# CRD.net
KiCad netlist of a schematic drawn in EAGLE
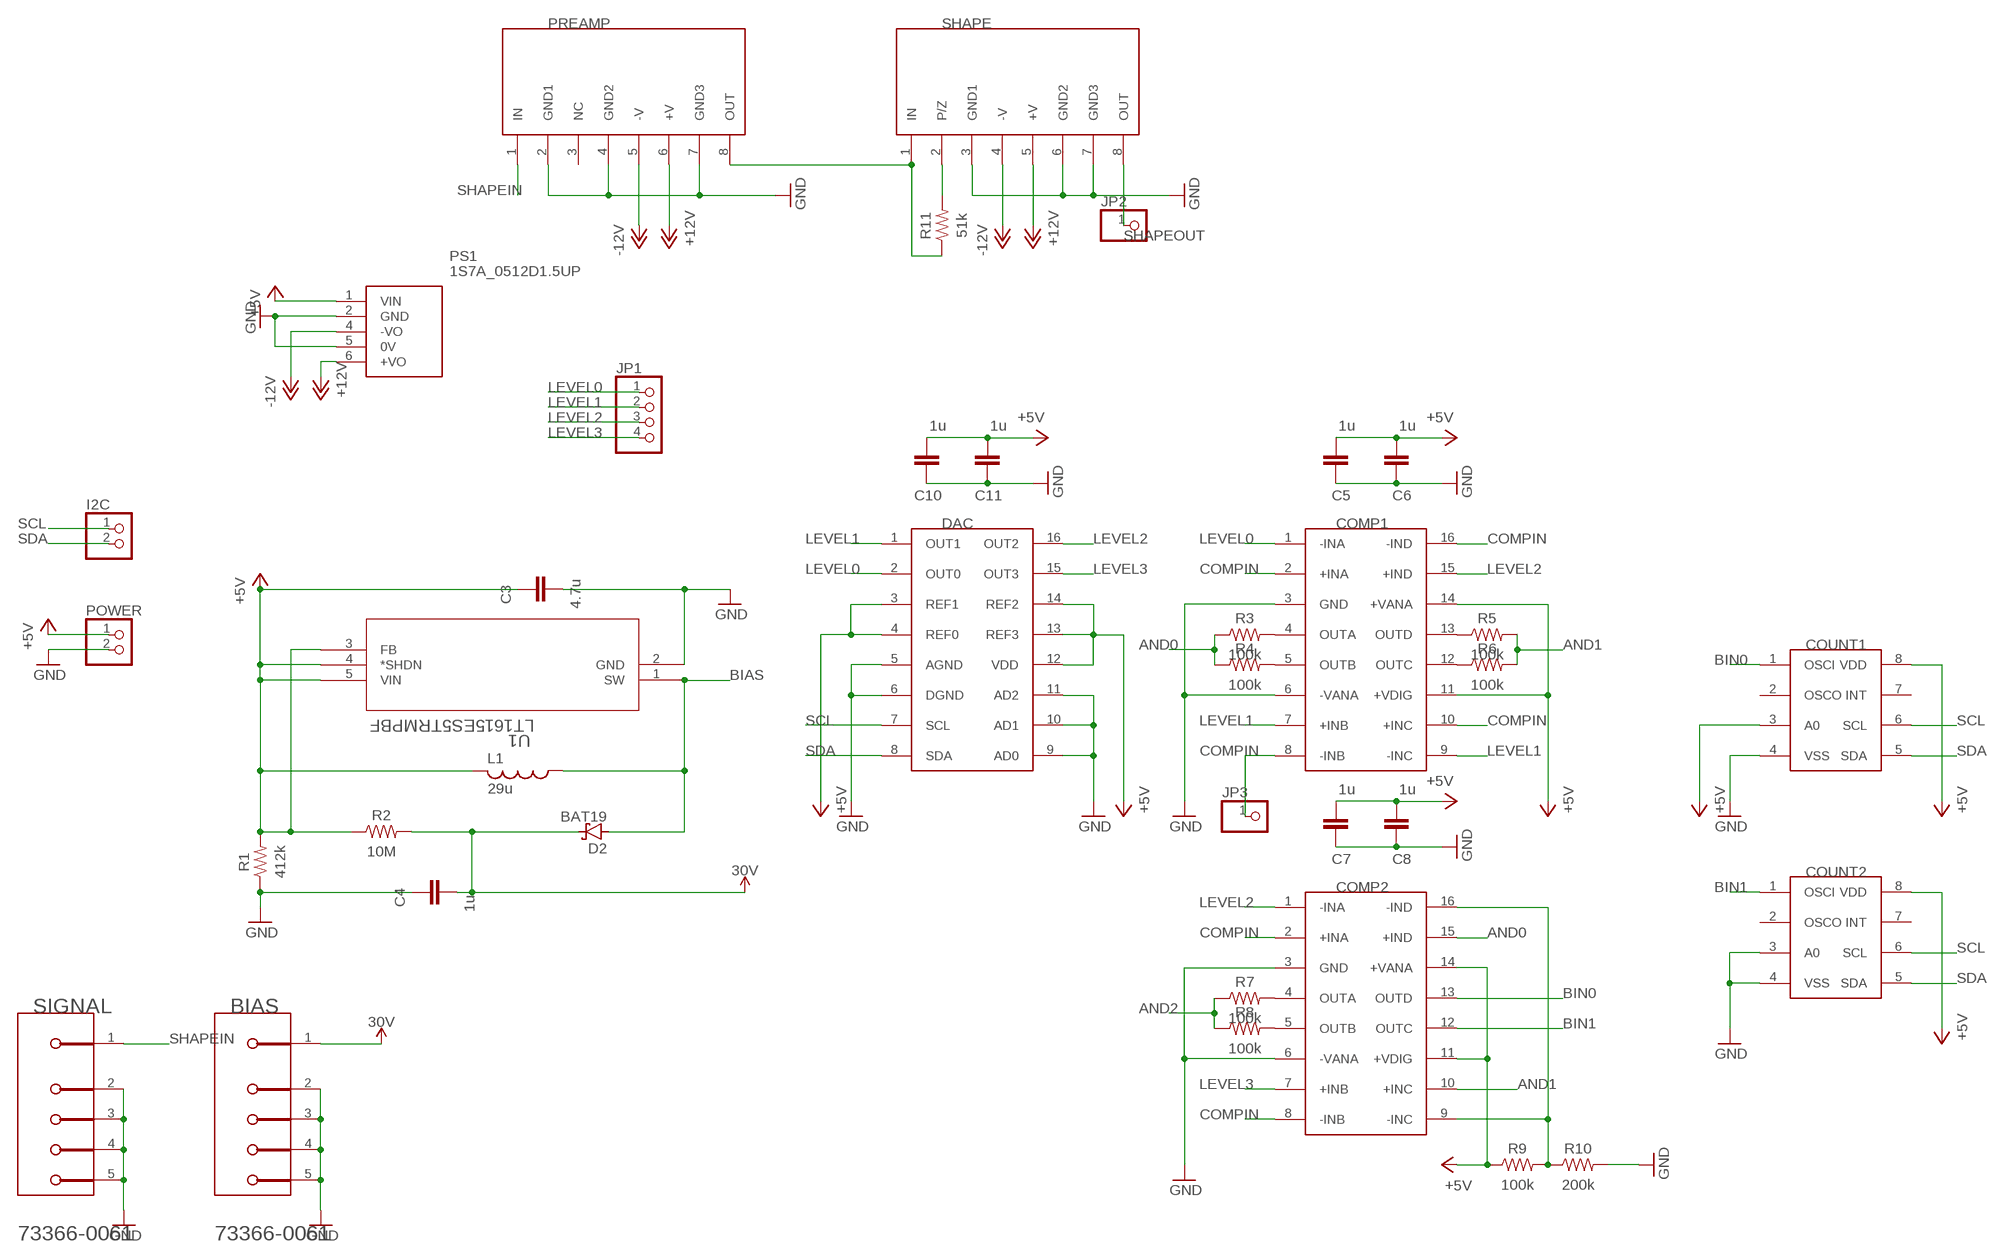
[diagram p0: schematic, sheet 1]

(export (version "E")
  (design (tool "Eeschema 10.0.6"))
  (components
    (comp (ref "BIAS")
      (value "MOLEX_73366-0061MOLEX_73366-0061_0_0")
      (footprint "eagle-import:MOLEX_73366-0061_0")
      (fields
        (field (name "DIGIKEY_PART_NUMBER") "WM5541-ND")
        (field (name "MF") "Molex")
        (field (name "MOUSER_PART_NUMBER") "538-73366-0061")
      )
      (libsource (lib "eagle-import") (part "MOLEX_73366-0061MOLEX_73366-0061_0_0"))
    )
    (comp (ref "C3")
      (value "4.7u")
      (footprint "eagle-import:CAP_1206")
      (fields
        (field (name "DIGIKEY_PART_NUMBER") "GRM31CR60J107ME39L")
        (field (name "MANUFACTURER") "Murata Electronics North America")
        (field (name "CREATED_BY") "PCBLayout.com")
      )
      (libsource (lib "eagle-import") (part "GRM31CR60J107ME39L"))
    )
    (comp (ref "C4")
      (value "1u")
      (footprint "eagle-import:CAP_1206")
      (fields
        (field (name "DIGIKEY_PART_NUMBER") "GRM31CR60J107ME39L")
        (field (name "MANUFACTURER") "Murata Electronics North America")
        (field (name "CREATED_BY") "PCBLayout.com")
      )
      (libsource (lib "eagle-import") (part "GRM31CR60J107ME39L"))
    )
    (comp (ref "C5")
      (value "1u")
      (footprint "eagle-import:CAP_1206")
      (fields
        (field (name "DIGIKEY_PART_NUMBER") "GRM31CR60J107ME39L")
        (field (name "MANUFACTURER") "Murata Electronics North America")
        (field (name "CREATED_BY") "PCBLayout.com")
      )
      (libsource (lib "eagle-import") (part "GRM31CR60J107ME39L"))
    )
    (comp (ref "C6")
      (value "1u")
      (footprint "eagle-import:CAP_1206")
      (fields
        (field (name "DIGIKEY_PART_NUMBER") "GRM31CR60J107ME39L")
        (field (name "MANUFACTURER") "Murata Electronics North America")
        (field (name "CREATED_BY") "PCBLayout.com")
      )
      (libsource (lib "eagle-import") (part "GRM31CR60J107ME39L"))
    )
    (comp (ref "C7")
      (value "1u")
      (footprint "eagle-import:CAP_1206")
      (fields
        (field (name "DIGIKEY_PART_NUMBER") "GRM31CR60J107ME39L")
        (field (name "MANUFACTURER") "Murata Electronics North America")
        (field (name "CREATED_BY") "PCBLayout.com")
      )
      (libsource (lib "eagle-import") (part "GRM31CR60J107ME39L"))
    )
    (comp (ref "C8")
      (value "1u")
      (footprint "eagle-import:CAP_1206")
      (fields
        (field (name "DIGIKEY_PART_NUMBER") "GRM31CR60J107ME39L")
        (field (name "MANUFACTURER") "Murata Electronics North America")
        (field (name "CREATED_BY") "PCBLayout.com")
      )
      (libsource (lib "eagle-import") (part "GRM31CR60J107ME39L"))
    )
    (comp (ref "C10")
      (value "1u")
      (footprint "eagle-import:CAP_1206")
      (fields
        (field (name "DIGIKEY_PART_NUMBER") "GRM31CR60J107ME39L")
        (field (name "MANUFACTURER") "Murata Electronics North America")
        (field (name "CREATED_BY") "PCBLayout.com")
      )
      (libsource (lib "eagle-import") (part "GRM31CR60J107ME39L"))
    )
    (comp (ref "C11")
      (value "1u")
      (footprint "eagle-import:CAP_1206")
      (fields
        (field (name "DIGIKEY_PART_NUMBER") "GRM31CR60J107ME39L")
        (field (name "MANUFACTURER") "Murata Electronics North America")
        (field (name "CREATED_BY") "PCBLayout.com")
      )
      (libsource (lib "eagle-import") (part "GRM31CR60J107ME39L"))
    )
    (comp (ref "COMP1")
      (value "AD8564ARZ")
      (footprint "eagle-import:SOIC127P1032X265-16N")
      (libsource (lib "eagle-import") (part "AD8564ARZ"))
    )
    (comp (ref "COMP2")
      (value "AD8564ARZ")
      (footprint "eagle-import:SOIC127P1032X265-16N")
      (libsource (lib "eagle-import") (part "AD8564ARZ"))
    )
    (comp (ref "COUNT1")
      (value "PCF8583")
      (footprint "eagle-import:SOIC127P1032X265-8N")
      (libsource (lib "eagle-import") (part "PCF8583"))
    )
    (comp (ref "COUNT2")
      (value "PCF8583")
      (footprint "eagle-import:SOIC127P1032X265-8N")
      (libsource (lib "eagle-import") (part "PCF8583"))
    )
    (comp (ref "D2")
      (value "BAT19")
      (footprint "eagle-import:DO35-10")
      (libsource (lib "eagle-import") (part "BAT19"))
    )
    (comp (ref "DAC")
      (value "MAX520BEWE+")
      (footprint "eagle-import:SOIC127P1032X265-16N")
      (libsource (lib "eagle-import") (part "MAX520BEWE+"))
    )
    (comp (ref "I2C")
      (value "PINHD-1X2")
      (footprint "eagle-import:1X02")
      (libsource (lib "eagle-import") (part "PINHD-1X2"))
    )
    (comp (ref "JP1")
      (value "PINHD-1X4")
      (footprint "eagle-import:1X04")
      (libsource (lib "eagle-import") (part "PINHD-1X4"))
    )
    (comp (ref "JP2")
      (value "PINHD-1X1")
      (footprint "eagle-import:1X01")
      (libsource (lib "eagle-import") (part "PINHD-1X1"))
    )
    (comp (ref "JP3")
      (value "PINHD-1X1")
      (footprint "eagle-import:1X01")
      (libsource (lib "eagle-import") (part "PINHD-1X1"))
    )
    (comp (ref "L1")
      (value "29u")
      (footprint "eagle-import:L1812")
      (libsource (lib "eagle-import") (part "L-USL1812"))
    )
    (comp (ref "POWER")
      (value "PINHD-1X2")
      (footprint "eagle-import:1X02")
      (libsource (lib "eagle-import") (part "PINHD-1X2"))
    )
    (comp (ref "PREAMP")
      (value "CR-113")
      (footprint "eagle-import:HDRV8W64P254_1X8_1016X508X838B")
      (libsource (lib "eagle-import") (part "CR-113"))
    )
    (comp (ref "PS1")
      (value "1S7A_0512D1.5UP")
      (footprint "eagle-import:1S7A_0505D15UP")
      (libsource (lib "eagle-import") (part "1S7A_0512D1.5UP"))
    )
    (comp (ref "R1")
      (value "412k")
      (footprint "eagle-import:RESAD1176W63L850D250B")
      (libsource (lib "eagle-import") (part "R-USAXIAL-11.7MM-PITCH_"))
    )
    (comp (ref "R2")
      (value "10M")
      (footprint "eagle-import:RESAD1176W63L850D250B")
      (libsource (lib "eagle-import") (part "R-USAXIAL-11.7MM-PITCH_"))
    )
    (comp (ref "R3")
      (value "100k")
      (footprint "eagle-import:RESAD1176W63L850D250B")
      (libsource (lib "eagle-import") (part "R-USAXIAL-11.7MM-PITCH_"))
    )
    (comp (ref "R4")
      (value "100k")
      (footprint "eagle-import:RESAD1176W63L850D250B")
      (libsource (lib "eagle-import") (part "R-USAXIAL-11.7MM-PITCH_"))
    )
    (comp (ref "R5")
      (value "100k")
      (footprint "eagle-import:RESAD1176W63L850D250B")
      (libsource (lib "eagle-import") (part "R-USAXIAL-11.7MM-PITCH_"))
    )
    (comp (ref "R6")
      (value "100k")
      (footprint "eagle-import:RESAD1176W63L850D250B")
      (libsource (lib "eagle-import") (part "R-USAXIAL-11.7MM-PITCH_"))
    )
    (comp (ref "R7")
      (value "100k")
      (footprint "eagle-import:RESAD1176W63L850D250B")
      (libsource (lib "eagle-import") (part "R-USAXIAL-11.7MM-PITCH_"))
    )
    (comp (ref "R8")
      (value "100k")
      (footprint "eagle-import:RESAD1176W63L850D250B")
      (libsource (lib "eagle-import") (part "R-USAXIAL-11.7MM-PITCH_"))
    )
    (comp (ref "R9")
      (value "100k")
      (footprint "eagle-import:RESAD1176W63L850D250B")
      (libsource (lib "eagle-import") (part "R-USAXIAL-11.7MM-PITCH_"))
    )
    (comp (ref "R10")
      (value "200k")
      (footprint "eagle-import:RESAD1176W63L850D250B")
      (libsource (lib "eagle-import") (part "R-USAXIAL-11.7MM-PITCH_"))
    )
    (comp (ref "R11")
      (value "51k")
      (footprint "eagle-import:RESAD1176W63L850D250B")
      (libsource (lib "eagle-import") (part "R-USAXIAL-11.7MM-PITCH_"))
    )
    (comp (ref "SHAPE")
      (value "CR-200")
      (footprint "eagle-import:HDRV8W64P254_1X8_1016X508X838B")
      (libsource (lib "eagle-import") (part "CR-200"))
    )
    (comp (ref "SIGNAL")
      (value "MOLEX_73366-0061MOLEX_73366-0061_0_0")
      (footprint "eagle-import:MOLEX_73366-0061_0")
      (fields
        (field (name "DIGIKEY_PART_NUMBER") "WM5541-ND")
        (field (name "MF") "Molex")
        (field (name "MOUSER_PART_NUMBER") "538-73366-0061")
      )
      (libsource (lib "eagle-import") (part "MOLEX_73366-0061MOLEX_73366-0061_0_0"))
    )
    (comp (ref "U1")
      (value "LT1615ES5TRMPBF")
      (footprint "eagle-import:SOT-5_S")
      (fields
        (field (name "DIGI-KEY_PART_NUMBER") "LT1615ES5#TRMPBFCT-ND")
        (field (name "MF") "Analog Devices")
        (field (name "MP") "LT1615ES5#TRMPBF")
      )
      (libsource (lib "eagle-import") (part "LT1615ES5TRMPBF"))
    )
  )
  (nets
    (net (code "1") (name "+5V") (class "Default")
      (node (ref "C10") (pin "2") (pinfunction "2_2") (pintype "passive"))
      (node (ref "C11") (pin "2") (pinfunction "2_2") (pintype "passive"))
      (node (ref "C3") (pin "1") (pinfunction "1_1") (pintype "passive"))
      (node (ref "C5") (pin "2") (pinfunction "2_2") (pintype "passive"))
      (node (ref "C6") (pin "2") (pinfunction "2_2") (pintype "passive"))
      (node (ref "C7") (pin "2") (pinfunction "2_2") (pintype "passive"))
      (node (ref "C8") (pin "2") (pinfunction "2_2") (pintype "passive"))
      (node (ref "COMP1") (pin "11") (pinfunction "+VDIG_11") (pintype "bidirectional"))
      (node (ref "COMP1") (pin "14") (pinfunction "+VANA_14") (pintype "bidirectional"))
      (node (ref "COMP2") (pin "11") (pinfunction "+VDIG_11") (pintype "bidirectional"))
      (node (ref "COMP2") (pin "14") (pinfunction "+VANA_14") (pintype "bidirectional"))
      (node (ref "COUNT1") (pin "3") (pinfunction "A0_3") (pintype "bidirectional"))
      (node (ref "COUNT1") (pin "8") (pinfunction "VDD_8") (pintype "bidirectional"))
      (node (ref "COUNT2") (pin "8") (pinfunction "VDD_8") (pintype "bidirectional"))
      (node (ref "DAC") (pin "12") (pinfunction "VDD_12") (pintype "bidirectional"))
      (node (ref "DAC") (pin "13") (pinfunction "REF3_13") (pintype "bidirectional"))
      (node (ref "DAC") (pin "14") (pinfunction "REF2_14") (pintype "bidirectional"))
      (node (ref "DAC") (pin "3") (pinfunction "REF1_3") (pintype "bidirectional"))
      (node (ref "DAC") (pin "4") (pinfunction "REF0_4") (pintype "bidirectional"))
      (node (ref "L1") (pin "2") (pinfunction "2_2") (pintype "passive"))
      (node (ref "POWER") (pin "1") (pinfunction "1_1") (pintype "passive"))
      (node (ref "PS1") (pin "1") (pinfunction "VIN_1") (pintype "bidirectional"))
      (node (ref "R1") (pin "2") (pinfunction "2_2") (pintype "passive"))
      (node (ref "R2") (pin "1") (pinfunction "1_1") (pintype "passive"))
      (node (ref "R9") (pin "1") (pinfunction "1_1") (pintype "passive"))
      (node (ref "U1") (pin "3") (pinfunction "FB_3") (pintype "passive"))
      (node (ref "U1") (pin "4") (pinfunction "*SHDN_4") (pintype "passive"))
      (node (ref "U1") (pin "5") (pinfunction "VIN_5") (pintype "input"))
    )
    (net (code "2") (name "+12V") (class "Default")
      (node (ref "PREAMP") (pin "6") (pinfunction "+V_6") (pintype "bidirectional"))
      (node (ref "PS1") (pin "6") (pinfunction "+VO_6") (pintype "bidirectional"))
      (node (ref "SHAPE") (pin "5") (pinfunction "+V_5") (pintype "bidirectional"))
    )
    (net (code "3") (name "-12V") (class "Default")
      (node (ref "PREAMP") (pin "5") (pinfunction "-V_5") (pintype "bidirectional"))
      (node (ref "PS1") (pin "4") (pinfunction "-VO_4") (pintype "bidirectional"))
      (node (ref "SHAPE") (pin "4") (pinfunction "-V_4") (pintype "bidirectional"))
    )
    (net (code "4") (name "/AND0") (class "Default")
      (node (ref "COMP2") (pin "15") (pinfunction "+IND_15") (pintype "bidirectional"))
      (node (ref "R3") (pin "1") (pinfunction "1_1") (pintype "passive"))
      (node (ref "R4") (pin "1") (pinfunction "1_1") (pintype "passive"))
    )
    (net (code "5") (name "/AND1") (class "Default")
      (node (ref "COMP2") (pin "10") (pinfunction "+INC_10") (pintype "bidirectional"))
      (node (ref "R5") (pin "2") (pinfunction "2_2") (pintype "passive"))
      (node (ref "R6") (pin "2") (pinfunction "2_2") (pintype "passive"))
    )
    (net (code "6") (name "/AND2") (class "Default")
      (node (ref "R7") (pin "1") (pinfunction "1_1") (pintype "passive"))
      (node (ref "R8") (pin "1") (pinfunction "1_1") (pintype "passive"))
    )
    (net (code "7") (name "/BIAS") (class "Default")
      (node (ref "D2") (pin "A") (pinfunction "A_A") (pintype "passive"))
      (node (ref "L1") (pin "1") (pinfunction "1_1") (pintype "passive"))
      (node (ref "U1") (pin "1") (pinfunction "SW_1") (pintype "passive"))
    )
    (net (code "8") (name "/BIN0") (class "Default")
      (node (ref "COMP2") (pin "13") (pinfunction "OUTD_13") (pintype "bidirectional"))
      (node (ref "COUNT1") (pin "1") (pinfunction "OSCI_1") (pintype "bidirectional"))
    )
    (net (code "9") (name "/BIN1") (class "Default")
      (node (ref "COMP2") (pin "12") (pinfunction "OUTC_12") (pintype "bidirectional"))
      (node (ref "COUNT2") (pin "1") (pinfunction "OSCI_1") (pintype "bidirectional"))
    )
    (net (code "10") (name "/COMPIN") (class "Default")
      (node (ref "COMP1") (pin "10") (pinfunction "+INC_10") (pintype "bidirectional"))
      (node (ref "COMP1") (pin "16") (pinfunction "-IND_16") (pintype "bidirectional"))
      (node (ref "COMP1") (pin "2") (pinfunction "+INA_2") (pintype "bidirectional"))
      (node (ref "COMP1") (pin "8") (pinfunction "-INB_8") (pintype "bidirectional"))
      (node (ref "COMP2") (pin "2") (pinfunction "+INA_2") (pintype "bidirectional"))
      (node (ref "COMP2") (pin "8") (pinfunction "-INB_8") (pintype "bidirectional"))
      (node (ref "JP3") (pin "1") (pinfunction "1_1") (pintype "passive"))
    )
    (net (code "11") (name "/LEVEL0") (class "Default")
      (node (ref "COMP1") (pin "1") (pinfunction "-INA_1") (pintype "bidirectional"))
      (node (ref "DAC") (pin "2") (pinfunction "OUT0_2") (pintype "bidirectional"))
      (node (ref "JP1") (pin "1") (pinfunction "1_1") (pintype "passive"))
    )
    (net (code "12") (name "/LEVEL1") (class "Default")
      (node (ref "COMP1") (pin "7") (pinfunction "+INB_7") (pintype "bidirectional"))
      (node (ref "COMP1") (pin "9") (pinfunction "-INC_9") (pintype "bidirectional"))
      (node (ref "DAC") (pin "1") (pinfunction "OUT1_1") (pintype "bidirectional"))
      (node (ref "JP1") (pin "2") (pinfunction "2_2") (pintype "passive"))
    )
    (net (code "13") (name "/LEVEL2") (class "Default")
      (node (ref "COMP1") (pin "15") (pinfunction "+IND_15") (pintype "bidirectional"))
      (node (ref "COMP2") (pin "1") (pinfunction "-INA_1") (pintype "bidirectional"))
      (node (ref "DAC") (pin "16") (pinfunction "OUT2_16") (pintype "bidirectional"))
      (node (ref "JP1") (pin "3") (pinfunction "3_3") (pintype "passive"))
    )
    (net (code "14") (name "/LEVEL3") (class "Default")
      (node (ref "COMP2") (pin "7") (pinfunction "+INB_7") (pintype "bidirectional"))
      (node (ref "DAC") (pin "15") (pinfunction "OUT3_15") (pintype "bidirectional"))
      (node (ref "JP1") (pin "4") (pinfunction "4_4") (pintype "passive"))
    )
    (net (code "15") (name "/SCL") (class "Default")
      (node (ref "COUNT1") (pin "6") (pinfunction "SCL_6") (pintype "bidirectional"))
      (node (ref "COUNT2") (pin "6") (pinfunction "SCL_6") (pintype "bidirectional"))
      (node (ref "DAC") (pin "7") (pinfunction "SCL_7") (pintype "bidirectional"))
      (node (ref "I2C") (pin "1") (pinfunction "1_1") (pintype "passive"))
    )
    (net (code "16") (name "/SDA") (class "Default")
      (node (ref "COUNT1") (pin "5") (pinfunction "SDA_5") (pintype "bidirectional"))
      (node (ref "COUNT2") (pin "5") (pinfunction "SDA_5") (pintype "bidirectional"))
      (node (ref "DAC") (pin "8") (pinfunction "SDA_8") (pintype "bidirectional"))
      (node (ref "I2C") (pin "2") (pinfunction "2_2") (pintype "passive"))
    )
    (net (code "17") (name "/SHAPEIN") (class "Default")
      (node (ref "PREAMP") (pin "1") (pinfunction "IN_1") (pintype "bidirectional"))
      (node (ref "SIGNAL") (pin "1") (pinfunction "1_1") (pintype "passive"))
    )
    (net (code "18") (name "/SHAPEOUT") (class "Default")
      (node (ref "JP2") (pin "1") (pinfunction "1_1") (pintype "passive"))
      (node (ref "SHAPE") (pin "8") (pinfunction "OUT_8") (pintype "bidirectional"))
    )
    (net (code "19") (name "30V") (class "Default")
      (node (ref "BIAS") (pin "1") (pinfunction "1_1") (pintype "passive"))
      (node (ref "C4") (pin "2") (pinfunction "2_2") (pintype "passive"))
      (node (ref "D2") (pin "C") (pinfunction "C_C") (pintype "passive"))
      (node (ref "R2") (pin "2") (pinfunction "2_2") (pintype "passive"))
    )
    (net (code "20") (name "GND") (class "Default")
      (node (ref "BIAS") (pin "2") (pinfunction "MNT_1_2") (pintype "passive"))
      (node (ref "BIAS") (pin "3") (pinfunction "MNT_2_3") (pintype "passive"))
      (node (ref "BIAS") (pin "4") (pinfunction "MNT_3_4") (pintype "passive"))
      (node (ref "BIAS") (pin "5") (pinfunction "MNT_4_5") (pintype "passive"))
      (node (ref "C10") (pin "1") (pinfunction "1_1") (pintype "passive"))
      (node (ref "C11") (pin "1") (pinfunction "1_1") (pintype "passive"))
      (node (ref "C3") (pin "2") (pinfunction "2_2") (pintype "passive"))
      (node (ref "C4") (pin "1") (pinfunction "1_1") (pintype "passive"))
      (node (ref "C5") (pin "1") (pinfunction "1_1") (pintype "passive"))
      (node (ref "C6") (pin "1") (pinfunction "1_1") (pintype "passive"))
      (node (ref "C7") (pin "1") (pinfunction "1_1") (pintype "passive"))
      (node (ref "C8") (pin "1") (pinfunction "1_1") (pintype "passive"))
      (node (ref "COMP1") (pin "3") (pinfunction "GND_3") (pintype "bidirectional"))
      (node (ref "COMP1") (pin "6") (pinfunction "-VANA_6") (pintype "bidirectional"))
      (node (ref "COMP2") (pin "3") (pinfunction "GND_3") (pintype "bidirectional"))
      (node (ref "COMP2") (pin "6") (pinfunction "-VANA_6") (pintype "bidirectional"))
      (node (ref "COUNT1") (pin "4") (pinfunction "VSS_4") (pintype "bidirectional"))
      (node (ref "COUNT2") (pin "3") (pinfunction "A0_3") (pintype "bidirectional"))
      (node (ref "COUNT2") (pin "4") (pinfunction "VSS_4") (pintype "bidirectional"))
      (node (ref "DAC") (pin "10") (pinfunction "AD1_10") (pintype "bidirectional"))
      (node (ref "DAC") (pin "11") (pinfunction "AD2_11") (pintype "bidirectional"))
      (node (ref "DAC") (pin "5") (pinfunction "AGND_5") (pintype "bidirectional"))
      (node (ref "DAC") (pin "6") (pinfunction "DGND_6") (pintype "bidirectional"))
      (node (ref "DAC") (pin "9") (pinfunction "AD0_9") (pintype "bidirectional"))
      (node (ref "POWER") (pin "2") (pinfunction "2_2") (pintype "passive"))
      (node (ref "PREAMP") (pin "2") (pinfunction "GND1_2") (pintype "bidirectional"))
      (node (ref "PREAMP") (pin "4") (pinfunction "GND2_4") (pintype "bidirectional"))
      (node (ref "PREAMP") (pin "7") (pinfunction "GND3_7") (pintype "bidirectional"))
      (node (ref "PS1") (pin "2") (pinfunction "GND_2") (pintype "bidirectional"))
      (node (ref "PS1") (pin "5") (pinfunction "0V_5") (pintype "bidirectional"))
      (node (ref "R1") (pin "1") (pinfunction "1_1") (pintype "passive"))
      (node (ref "R10") (pin "2") (pinfunction "2_2") (pintype "passive"))
      (node (ref "SHAPE") (pin "3") (pinfunction "GND1_3") (pintype "bidirectional"))
      (node (ref "SHAPE") (pin "6") (pinfunction "GND2_6") (pintype "bidirectional"))
      (node (ref "SHAPE") (pin "7") (pinfunction "GND3_7") (pintype "bidirectional"))
      (node (ref "SIGNAL") (pin "2") (pinfunction "MNT_1_2") (pintype "passive"))
      (node (ref "SIGNAL") (pin "3") (pinfunction "MNT_2_3") (pintype "passive"))
      (node (ref "SIGNAL") (pin "4") (pinfunction "MNT_3_4") (pintype "passive"))
      (node (ref "SIGNAL") (pin "5") (pinfunction "MNT_4_5") (pintype "passive"))
      (node (ref "U1") (pin "2") (pinfunction "GND_2") (pintype "power_in"))
    )
    (net (code "21") (name "Net-(COMP1-OUTA)") (class "Default")
      (node (ref "COMP1") (pin "4") (pinfunction "OUTA_4") (pintype "bidirectional"))
      (node (ref "R3") (pin "2") (pinfunction "2_2") (pintype "passive"))
    )
    (net (code "22") (name "Net-(COMP1-OUTB)") (class "Default")
      (node (ref "COMP1") (pin "5") (pinfunction "OUTB_5") (pintype "bidirectional"))
      (node (ref "R4") (pin "2") (pinfunction "2_2") (pintype "passive"))
    )
    (net (code "23") (name "Net-(COMP1-OUTC)") (class "Default")
      (node (ref "COMP1") (pin "12") (pinfunction "OUTC_12") (pintype "bidirectional"))
      (node (ref "R6") (pin "1") (pinfunction "1_1") (pintype "passive"))
    )
    (net (code "24") (name "Net-(COMP1-OUTD)") (class "Default")
      (node (ref "COMP1") (pin "13") (pinfunction "OUTD_13") (pintype "bidirectional"))
      (node (ref "R5") (pin "1") (pinfunction "1_1") (pintype "passive"))
    )
    (net (code "25") (name "Net-(COMP2--INC)") (class "Default")
      (node (ref "COMP2") (pin "16") (pinfunction "-IND_16") (pintype "bidirectional"))
      (node (ref "COMP2") (pin "9") (pinfunction "-INC_9") (pintype "bidirectional"))
      (node (ref "R10") (pin "1") (pinfunction "1_1") (pintype "passive"))
      (node (ref "R9") (pin "2") (pinfunction "2_2") (pintype "passive"))
    )
    (net (code "26") (name "Net-(COMP2-OUTA)") (class "Default")
      (node (ref "COMP2") (pin "4") (pinfunction "OUTA_4") (pintype "bidirectional"))
      (node (ref "R7") (pin "2") (pinfunction "2_2") (pintype "passive"))
    )
    (net (code "27") (name "Net-(COMP2-OUTB)") (class "Default")
      (node (ref "COMP2") (pin "5") (pinfunction "OUTB_5") (pintype "bidirectional"))
      (node (ref "R8") (pin "2") (pinfunction "2_2") (pintype "passive"))
    )
    (net (code "28") (name "Net-(PREAMP-OUT)") (class "Default")
      (node (ref "PREAMP") (pin "8") (pinfunction "OUT_8") (pintype "bidirectional"))
      (node (ref "R11") (pin "1") (pinfunction "1_1") (pintype "passive"))
      (node (ref "SHAPE") (pin "1") (pinfunction "IN_1") (pintype "bidirectional"))
    )
    (net (code "29") (name "Net-(SHAPE-P{slash}Z)") (class "Default")
      (node (ref "R11") (pin "2") (pinfunction "2_2") (pintype "passive"))
      (node (ref "SHAPE") (pin "2") (pinfunction "P/Z_2") (pintype "bidirectional"))
    )
    (net (code "30") (name "unconnected-(COUNT1-INT-Pad7)") (class "Default")
      (node (ref "COUNT1") (pin "7") (pinfunction "INT_7") (pintype "bidirectional"))
    )
    (net (code "31") (name "unconnected-(COUNT1-OSCO-Pad2)") (class "Default")
      (node (ref "COUNT1") (pin "2") (pinfunction "OSCO_2") (pintype "bidirectional"))
    )
    (net (code "32") (name "unconnected-(COUNT2-INT-Pad7)") (class "Default")
      (node (ref "COUNT2") (pin "7") (pinfunction "INT_7") (pintype "bidirectional"))
    )
    (net (code "33") (name "unconnected-(COUNT2-OSCO-Pad2)") (class "Default")
      (node (ref "COUNT2") (pin "2") (pinfunction "OSCO_2") (pintype "bidirectional"))
    )
    (net (code "34") (name "unconnected-(PREAMP-NC-Pad3)") (class "Default")
      (node (ref "PREAMP") (pin "3") (pinfunction "NC_3") (pintype "bidirectional"))
    )
  )
)
